# BATT_INPUT.net
KiCad netlist of a schematic drawn in EAGLE
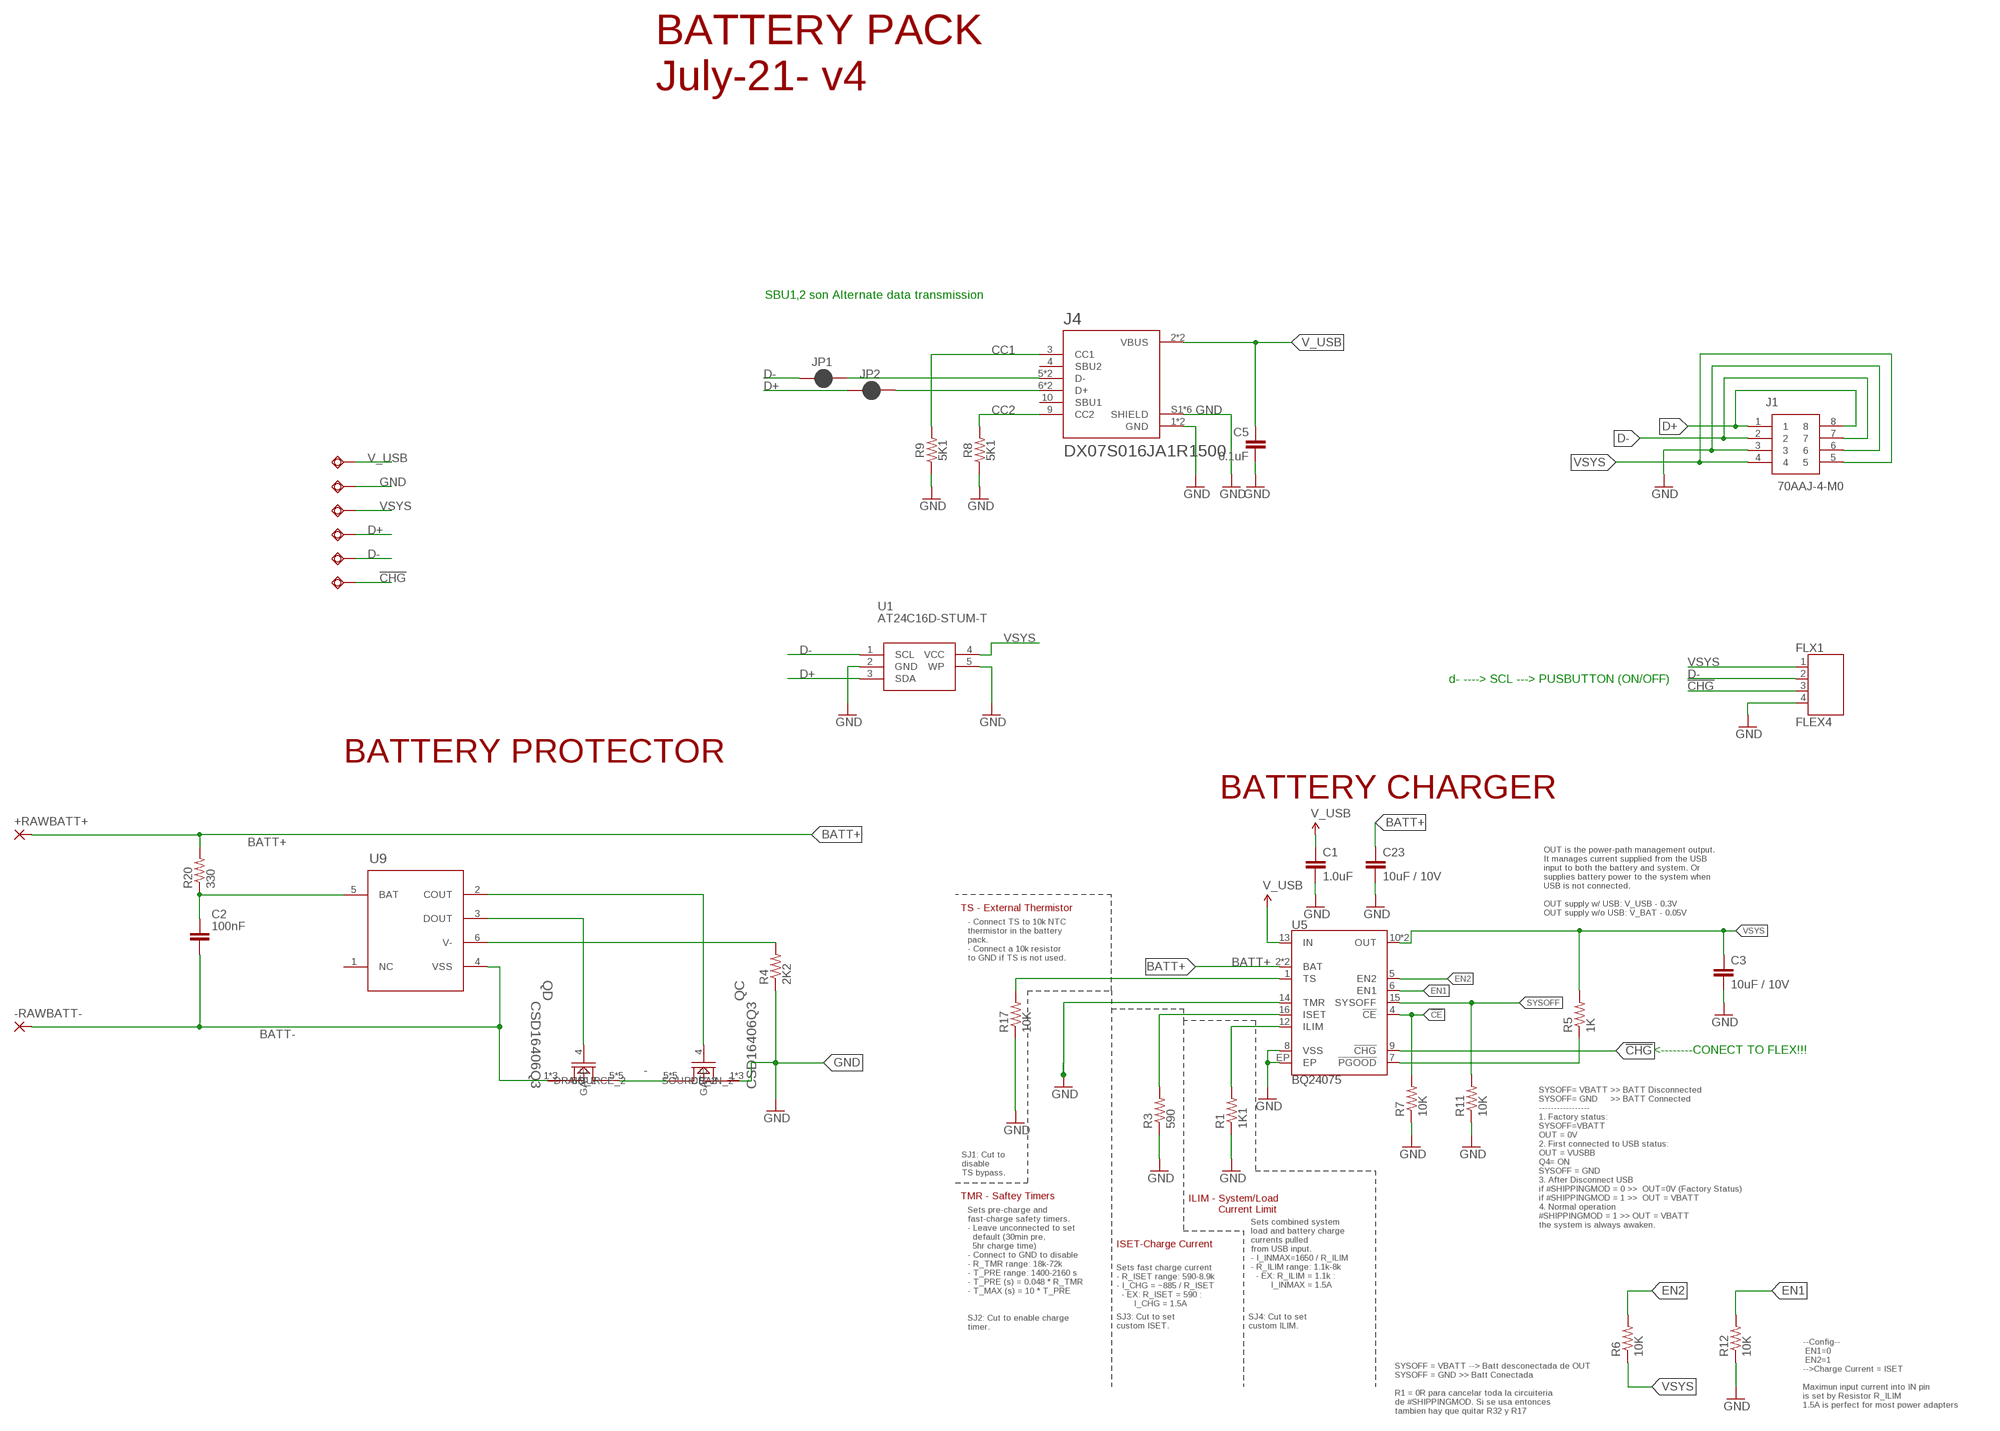
[diagram p0: schematic, sheet 1]

(export (version "E")
  (design (tool "Eeschema 10.0.6"))
  (components
    (comp (ref "!CHG!")
      (value "TESTPAD_TPSQB1,27")
      (footprint "eagle-import:TESTPAD_B1,27")
      (libsource (lib "eagle-import") (part "TESTPAD_TPSQB1,27"))
    )
    (comp (ref "+RAWBATT+")
      (value "SMD5")
      (footprint "eagle-import:SMD2,54-5,08")
      (libsource (lib "eagle-import") (part "SMD5"))
    )
    (comp (ref "-RAWBATT-")
      (value "SMD5")
      (footprint "eagle-import:SMD2,54-5,08")
      (libsource (lib "eagle-import") (part "SMD5"))
    )
    (comp (ref "C1")
      (value "1.0uF")
      (footprint "eagle-import:0603")
      (libsource (lib "eagle-import") (part "1.0UF-0603-16V-10%"))
    )
    (comp (ref "C2")
      (value "100nF")
      (footprint "eagle-import:CAPC1608X85")
      (libsource (lib "eagle-import") (part "CCHIP-0603(1608-METRIC)_"))
    )
    (comp (ref "C3")
      (value "10uF / 10V")
      (footprint "eagle-import:0805-CAP")
      (libsource (lib "eagle-import") (part "10UF10V10%(0805)"))
    )
    (comp (ref "C5")
      (value "0.1uF")
      (footprint "eagle-import:0603")
      (libsource (lib "eagle-import") (part "0.1UF-0603-25V-(+80/-20%)"))
    )
    (comp (ref "C23")
      (value "10uF / 10V")
      (footprint "eagle-import:0805-CAP")
      (libsource (lib "eagle-import") (part "10UF10V10%(0805)"))
    )
    (comp (ref "D+")
      (value "TESTPAD_TPSQB1,27")
      (footprint "eagle-import:TESTPAD_B1,27")
      (libsource (lib "eagle-import") (part "TESTPAD_TPSQB1,27"))
    )
    (comp (ref "D-")
      (value "TESTPAD_TPSQB1,27")
      (footprint "eagle-import:TESTPAD_B1,27")
      (libsource (lib "eagle-import") (part "TESTPAD_TPSQB1,27"))
    )
    (comp (ref "FLX1")
      (value "FLEX4")
      (footprint "eagle-import:FLEX4")
      (libsource (lib "eagle-import") (part "FLEX4"))
    )
    (comp (ref "GND")
      (value "TESTPAD_TPSQB1,27")
      (footprint "eagle-import:TESTPAD_B1,27")
      (libsource (lib "eagle-import") (part "TESTPAD_TPSQB1,27"))
    )
    (comp (ref "J1")
      (value "70AAJ-4-M0")
      (footprint "eagle-import:70AAJ4M0")
      (fields (field (name "MOUSER_PART_NUMBER") "652-70AAJ-4-M0"))
      (libsource (lib "eagle-import") (part "70AAJ-4-M0"))
    )
    (comp (ref "J4")
      (value "DX07S016JA1R1500")
      (footprint "eagle-import:JAE_DX07S016JA1R1500")
      (fields
        (field (name "DIGI-KEY_PART_NUMBER") "670-DX07S016JA1R1500CT-ND")
        (field (name "MF") "JAE Electronics")
      )
      (libsource (lib "eagle-import") (part "DX07S016JA1R1500"))
    )
    (comp (ref "JP1")
      (value "JUMPER-SMT_2_NC_PASTE_SILK")
      (footprint "eagle-import:SMT-JUMPER_2_NC_PASTE_SILK")
      (libsource (lib "eagle-import") (part "JUMPER-SMT_2_NC_PASTE_SILK"))
    )
    (comp (ref "JP2")
      (value "JUMPER-SMT_2_NC_PASTE_SILK")
      (footprint "eagle-import:SMT-JUMPER_2_NC_PASTE_SILK")
      (libsource (lib "eagle-import") (part "JUMPER-SMT_2_NC_PASTE_SILK"))
    )
    (comp (ref "QC")
      (value "CSD16406Q3")
      (footprint "eagle-import:DQG0008A")
      (libsource (lib "eagle-import") (part "CSD16406Q3"))
    )
    (comp (ref "QD")
      (value "CSD16406Q3")
      (footprint "eagle-import:DQG0008A")
      (libsource (lib "eagle-import") (part "CSD16406Q3"))
    )
    (comp (ref "R1")
      (value "1K1")
      (footprint "eagle-import:0402")
      (libsource (lib "eagle-import") (part "RESISTOR0402"))
    )
    (comp (ref "R3")
      (value "590")
      (footprint "eagle-import:0402")
      (libsource (lib "eagle-import") (part "RESISTOR0402"))
    )
    (comp (ref "R4")
      (value "2K2")
      (footprint "eagle-import:0402")
      (libsource (lib "eagle-import") (part "RESISTOR0402"))
    )
    (comp (ref "R5")
      (value "1K")
      (footprint "eagle-import:0402")
      (libsource (lib "eagle-import") (part "RESISTOR0402"))
    )
    (comp (ref "R6")
      (value "10K")
      (footprint "eagle-import:0402")
      (libsource (lib "eagle-import") (part "RESISTOR0402"))
    )
    (comp (ref "R7")
      (value "10K")
      (footprint "eagle-import:0402")
      (libsource (lib "eagle-import") (part "RESISTOR0402"))
    )
    (comp (ref "R8")
      (value "5K1")
      (footprint "eagle-import:0402")
      (libsource (lib "eagle-import") (part "RESISTOR0402"))
    )
    (comp (ref "R9")
      (value "5K1")
      (footprint "eagle-import:0402")
      (libsource (lib "eagle-import") (part "RESISTOR0402"))
    )
    (comp (ref "R11")
      (value "10K")
      (footprint "eagle-import:0402")
      (libsource (lib "eagle-import") (part "RESISTOR0402"))
    )
    (comp (ref "R12")
      (value "10K")
      (footprint "eagle-import:0402")
      (libsource (lib "eagle-import") (part "RESISTOR0402"))
    )
    (comp (ref "R17")
      (value "10K")
      (footprint "eagle-import:0402")
      (libsource (lib "eagle-import") (part "RESISTOR0402"))
    )
    (comp (ref "R20")
      (value "330")
      (footprint "eagle-import:0402")
      (libsource (lib "eagle-import") (part "RESISTOR0402"))
    )
    (comp (ref "U1")
      (value "AT24C16D-STUM-T")
      (footprint "eagle-import:SOT95P280X100-5N")
      (fields (field (name "MOUSER_PART_NUMBER") "556-AT24C16D-STUM-T"))
      (libsource (lib "eagle-import") (part "AT24C16D-STUM-T"))
    )
    (comp (ref "U5")
      (value "BQ24075")
      (footprint "eagle-import:PVQFN-N16")
      (libsource (lib "eagle-import") (part "BQ24075"))
    )
    (comp (ref "U9")
      (value "Value")
      (footprint "eagle-import:DSE0006A")
      (fields (field (name "MANUFACTURER") "Texas Instruments") (field (name "PARTNUMBER") "BQ29705DSER"))
      (libsource (lib "eagle-import") (part "BQ29700DSER"))
    )
    (comp (ref "VSYS")
      (value "TESTPAD_TPSQB1,27")
      (footprint "eagle-import:TESTPAD_B1,27")
      (libsource (lib "eagle-import") (part "TESTPAD_TPSQB1,27"))
    )
    (comp (ref "V_USB")
      (value "TESTPAD_TPSQB1,27")
      (footprint "eagle-import:TESTPAD_B1,27")
      (libsource (lib "eagle-import") (part "TESTPAD_TPSQB1,27"))
    )
  )
  (nets
    (net (code "1") (name "/-") (class "Default")
      (node (ref "QC") (pin "5") (pinfunction "DRAIN_2_5") (pintype "passive"))
      (node (ref "QC") (pin "6") (pinfunction "DRAIN_2_6") (pintype "passive"))
      (node (ref "QC") (pin "7") (pinfunction "DRAIN_2_7") (pintype "passive"))
      (node (ref "QC") (pin "8") (pinfunction "DRAIN_2_8") (pintype "passive"))
      (node (ref "QC") (pin "9") (pinfunction "DRAIN_2_9") (pintype "passive"))
      (node (ref "QD") (pin "5") (pinfunction "DRAIN_2_5") (pintype "passive"))
      (node (ref "QD") (pin "6") (pinfunction "DRAIN_2_6") (pintype "passive"))
      (node (ref "QD") (pin "7") (pinfunction "DRAIN_2_7") (pintype "passive"))
      (node (ref "QD") (pin "8") (pinfunction "DRAIN_2_8") (pintype "passive"))
      (node (ref "QD") (pin "9") (pinfunction "DRAIN_2_9") (pintype "passive"))
    )
    (net (code "2") (name "/BATT-") (class "Default")
      (node (ref "-RAWBATT-") (pin "1") (pinfunction "P_1") (pintype "passive"))
      (node (ref "C2") (pin "2") (pinfunction "2_2") (pintype "passive"))
      (node (ref "QD") (pin "1") (pinfunction "SOURCE_2_1") (pintype "passive"))
      (node (ref "QD") (pin "2") (pinfunction "SOURCE_2_2") (pintype "passive"))
      (node (ref "QD") (pin "3") (pinfunction "SOURCE_2_3") (pintype "passive"))
      (node (ref "U9") (pin "4") (pinfunction "VSS_4") (pintype "power_in"))
    )
    (net (code "3") (name "/CC1") (class "Default")
      (node (ref "J4") (pin "3") (pinfunction "CC1_3") (pintype "passive"))
      (node (ref "R9") (pin "2") (pinfunction "2_2") (pintype "passive"))
    )
    (net (code "4") (name "/CC2") (class "Default")
      (node (ref "J4") (pin "9") (pinfunction "CC2_9") (pintype "passive"))
      (node (ref "R8") (pin "2") (pinfunction "2_2") (pintype "passive"))
    )
    (net (code "5") (name "/~{CE}") (class "Default")
      (node (ref "R7") (pin "2") (pinfunction "2_2") (pintype "passive"))
      (node (ref "U5") (pin "4") (pinfunction "~{CE}_4") (pintype "bidirectional"))
    )
    (net (code "6") (name "/~{CHG}") (class "Default")
      (node (ref "!CHG!") (pin "TP") (pinfunction "TP_TP") (pintype "input"))
      (node (ref "FLX1") (pin "3") (pinfunction "3_3") (pintype "passive"))
      (node (ref "U5") (pin "9") (pinfunction "~{CHG}_9") (pintype "bidirectional"))
    )
    (net (code "7") (name "BATT+") (class "Default")
      (node (ref "+RAWBATT+") (pin "1") (pinfunction "P_1") (pintype "passive"))
      (node (ref "C23") (pin "1") (pinfunction "1_1") (pintype "passive"))
      (node (ref "R20") (pin "2") (pinfunction "2_2") (pintype "passive"))
      (node (ref "U5") (pin "2") (pinfunction "BAT_2") (pintype "bidirectional"))
      (node (ref "U5") (pin "3") (pinfunction "BAT_3") (pintype "bidirectional"))
    )
    (net (code "8") (name "D+") (class "Default")
      (node (ref "D+") (pin "TP") (pinfunction "TP_TP") (pintype "input"))
      (node (ref "J1") (pin "1") (pinfunction "1_1") (pintype "bidirectional"))
      (node (ref "J1") (pin "8") (pinfunction "8_8") (pintype "bidirectional"))
      (node (ref "JP2") (pin "1") (pinfunction "1_1") (pintype "passive"))
      (node (ref "U1") (pin "3") (pinfunction "SDA_3") (pintype "bidirectional"))
    )
    (net (code "9") (name "D-") (class "Default")
      (node (ref "D-") (pin "TP") (pinfunction "TP_TP") (pintype "input"))
      (node (ref "FLX1") (pin "2") (pinfunction "2_2") (pintype "passive"))
      (node (ref "J1") (pin "2") (pinfunction "2_2") (pintype "bidirectional"))
      (node (ref "J1") (pin "7") (pinfunction "7_7") (pintype "bidirectional"))
      (node (ref "JP1") (pin "1") (pinfunction "1_1") (pintype "passive"))
      (node (ref "U1") (pin "1") (pinfunction "SCL_1") (pintype "bidirectional"))
    )
    (net (code "10") (name "EN1") (class "Default")
      (node (ref "R12") (pin "2") (pinfunction "2_2") (pintype "passive"))
      (node (ref "U5") (pin "6") (pinfunction "EN1_6") (pintype "bidirectional"))
    )
    (net (code "11") (name "EN2") (class "Default")
      (node (ref "R6") (pin "2") (pinfunction "2_2") (pintype "passive"))
      (node (ref "U5") (pin "5") (pinfunction "EN2_5") (pintype "bidirectional"))
    )
    (net (code "12") (name "GND") (class "Default")
      (node (ref "C1") (pin "2") (pinfunction "2_2") (pintype "passive"))
      (node (ref "C23") (pin "2") (pinfunction "2_2") (pintype "passive"))
      (node (ref "C3") (pin "2") (pinfunction "2_2") (pintype "passive"))
      (node (ref "C5") (pin "2") (pinfunction "2_2") (pintype "passive"))
      (node (ref "FLX1") (pin "4") (pinfunction "4_4") (pintype "passive"))
      (node (ref "GND") (pin "TP") (pinfunction "TP_TP") (pintype "input"))
      (node (ref "J1") (pin "3") (pinfunction "3_3") (pintype "bidirectional"))
      (node (ref "J1") (pin "6") (pinfunction "6_6") (pintype "bidirectional"))
      (node (ref "J4") (pin "1") (pinfunction "GND_1") (pintype "power_in"))
      (node (ref "J4") (pin "12") (pinfunction "GND_12") (pintype "power_in"))
      (node (ref "J4") (pin "S1") (pinfunction "SHIELD_S1") (pintype "passive"))
      (node (ref "J4") (pin "S2") (pinfunction "SHIELD_S2") (pintype "passive"))
      (node (ref "J4") (pin "S3") (pinfunction "SHIELD_S3") (pintype "passive"))
      (node (ref "J4") (pin "S4") (pinfunction "SHIELD_S4") (pintype "passive"))
      (node (ref "J4") (pin "S5") (pinfunction "SHIELD_S5") (pintype "passive"))
      (node (ref "J4") (pin "S6") (pinfunction "SHIELD_S6") (pintype "passive"))
      (node (ref "QC") (pin "1") (pinfunction "SOURCE_2_1") (pintype "passive"))
      (node (ref "QC") (pin "2") (pinfunction "SOURCE_2_2") (pintype "passive"))
      (node (ref "QC") (pin "3") (pinfunction "SOURCE_2_3") (pintype "passive"))
      (node (ref "R1") (pin "1") (pinfunction "1_1") (pintype "passive"))
      (node (ref "R11") (pin "1") (pinfunction "1_1") (pintype "passive"))
      (node (ref "R12") (pin "1") (pinfunction "1_1") (pintype "passive"))
      (node (ref "R17") (pin "1") (pinfunction "1_1") (pintype "passive"))
      (node (ref "R3") (pin "1") (pinfunction "1_1") (pintype "passive"))
      (node (ref "R4") (pin "1") (pinfunction "1_1") (pintype "passive"))
      (node (ref "R7") (pin "1") (pinfunction "1_1") (pintype "passive"))
      (node (ref "R8") (pin "1") (pinfunction "1_1") (pintype "passive"))
      (node (ref "R9") (pin "1") (pinfunction "1_1") (pintype "passive"))
      (node (ref "U1") (pin "2") (pinfunction "GND_2") (pintype "power_in"))
      (node (ref "U1") (pin "5") (pinfunction "WP_5") (pintype "input"))
      (node (ref "U5") (pin "14") (pinfunction "TMR_14") (pintype "bidirectional"))
      (node (ref "U5") (pin "8") (pinfunction "VSS_8") (pintype "bidirectional"))
      (node (ref "U5") (pin "EP") (pinfunction "EP_EP") (pintype "bidirectional"))
    )
    (net (code "13") (name "Net-(J4-D+-Pad6)") (class "Default")
      (node (ref "J4") (pin "6") (pinfunction "D+_6") (pintype "passive"))
      (node (ref "J4") (pin "7") (pinfunction "D+_7") (pintype "passive"))
      (node (ref "JP2") (pin "2") (pinfunction "2_2") (pintype "passive"))
    )
    (net (code "14") (name "Net-(J4-D--Pad5)") (class "Default")
      (node (ref "J4") (pin "5") (pinfunction "D-_5") (pintype "passive"))
      (node (ref "J4") (pin "8") (pinfunction "D-_8") (pintype "passive"))
      (node (ref "JP1") (pin "2") (pinfunction "2_2") (pintype "passive"))
    )
    (net (code "15") (name "Net-(QC-GATE)") (class "Default")
      (node (ref "QC") (pin "4") (pinfunction "GATE_4") (pintype "passive"))
      (node (ref "U9") (pin "2") (pinfunction "COUT_2") (pintype "output"))
    )
    (net (code "16") (name "Net-(QD-GATE)") (class "Default")
      (node (ref "QD") (pin "4") (pinfunction "GATE_4") (pintype "passive"))
      (node (ref "U9") (pin "3") (pinfunction "DOUT_3") (pintype "output"))
    )
    (net (code "17") (name "Net-(U5-ILIM)") (class "Default")
      (node (ref "R1") (pin "2") (pinfunction "2_2") (pintype "passive"))
      (node (ref "U5") (pin "12") (pinfunction "ILIM_12") (pintype "bidirectional"))
    )
    (net (code "18") (name "Net-(U5-ISET)") (class "Default")
      (node (ref "R3") (pin "2") (pinfunction "2_2") (pintype "passive"))
      (node (ref "U5") (pin "16") (pinfunction "ISET_16") (pintype "bidirectional"))
    )
    (net (code "19") (name "Net-(U5-TS)") (class "Default")
      (node (ref "R17") (pin "2") (pinfunction "2_2") (pintype "passive"))
      (node (ref "U5") (pin "1") (pinfunction "TS_1") (pintype "bidirectional"))
    )
    (net (code "20") (name "Net-(U5-~{PGOOD})") (class "Default")
      (node (ref "R5") (pin "1") (pinfunction "1_1") (pintype "passive"))
      (node (ref "U5") (pin "7") (pinfunction "~{PGOOD}_7") (pintype "bidirectional"))
    )
    (net (code "21") (name "Net-(U9-BAT)") (class "Default")
      (node (ref "C2") (pin "1") (pinfunction "1_1") (pintype "passive"))
      (node (ref "R20") (pin "1") (pinfunction "1_1") (pintype "passive"))
      (node (ref "U9") (pin "5") (pinfunction "BAT_5") (pintype "power_in"))
    )
    (net (code "22") (name "Net-(U9-V-)") (class "Default")
      (node (ref "R4") (pin "2") (pinfunction "2_2") (pintype "passive"))
      (node (ref "U9") (pin "6") (pinfunction "V-_6") (pintype "bidirectional"))
    )
    (net (code "23") (name "SYSOFF") (class "Default")
      (node (ref "R11") (pin "2") (pinfunction "2_2") (pintype "passive"))
      (node (ref "U5") (pin "15") (pinfunction "SYSOFF_15") (pintype "bidirectional"))
    )
    (net (code "24") (name "VSYS") (class "Default")
      (node (ref "C3") (pin "1") (pinfunction "1_1") (pintype "passive"))
      (node (ref "FLX1") (pin "1") (pinfunction "1_1") (pintype "passive"))
      (node (ref "J1") (pin "4") (pinfunction "4_4") (pintype "bidirectional"))
      (node (ref "J1") (pin "5") (pinfunction "5_5") (pintype "bidirectional"))
      (node (ref "R5") (pin "2") (pinfunction "2_2") (pintype "passive"))
      (node (ref "R6") (pin "1") (pinfunction "1_1") (pintype "passive"))
      (node (ref "U1") (pin "4") (pinfunction "VCC_4") (pintype "power_in"))
      (node (ref "U5") (pin "10") (pinfunction "OUT_10") (pintype "bidirectional"))
      (node (ref "U5") (pin "11") (pinfunction "OUT_11") (pintype "bidirectional"))
      (node (ref "VSYS") (pin "TP") (pinfunction "TP_TP") (pintype "input"))
    )
    (net (code "25") (name "V_USB") (class "Default")
      (node (ref "C1") (pin "1") (pinfunction "1_1") (pintype "passive"))
      (node (ref "C5") (pin "1") (pinfunction "1_1") (pintype "passive"))
      (node (ref "J4") (pin "11") (pinfunction "VBUS_11") (pintype "power_in"))
      (node (ref "J4") (pin "2") (pinfunction "VBUS_2") (pintype "power_in"))
      (node (ref "U5") (pin "13") (pinfunction "IN_13") (pintype "bidirectional"))
      (node (ref "V_USB") (pin "TP") (pinfunction "TP_TP") (pintype "input"))
    )
    (net (code "26") (name "unconnected-(J4-SBU1-Pad10)") (class "Default")
      (node (ref "J4") (pin "10") (pinfunction "SBU1_10") (pintype "passive"))
    )
    (net (code "27") (name "unconnected-(J4-SBU2-Pad4)") (class "Default")
      (node (ref "J4") (pin "4") (pinfunction "SBU2_4") (pintype "passive"))
    )
    (net (code "28") (name "unconnected-(U9-NC-Pad1)") (class "Default")
      (node (ref "U9") (pin "1") (pinfunction "NC_1") (pintype "passive"))
    )
  )
)
